# CS_SNS.net
KiCad netlist of a schematic drawn in EAGLE
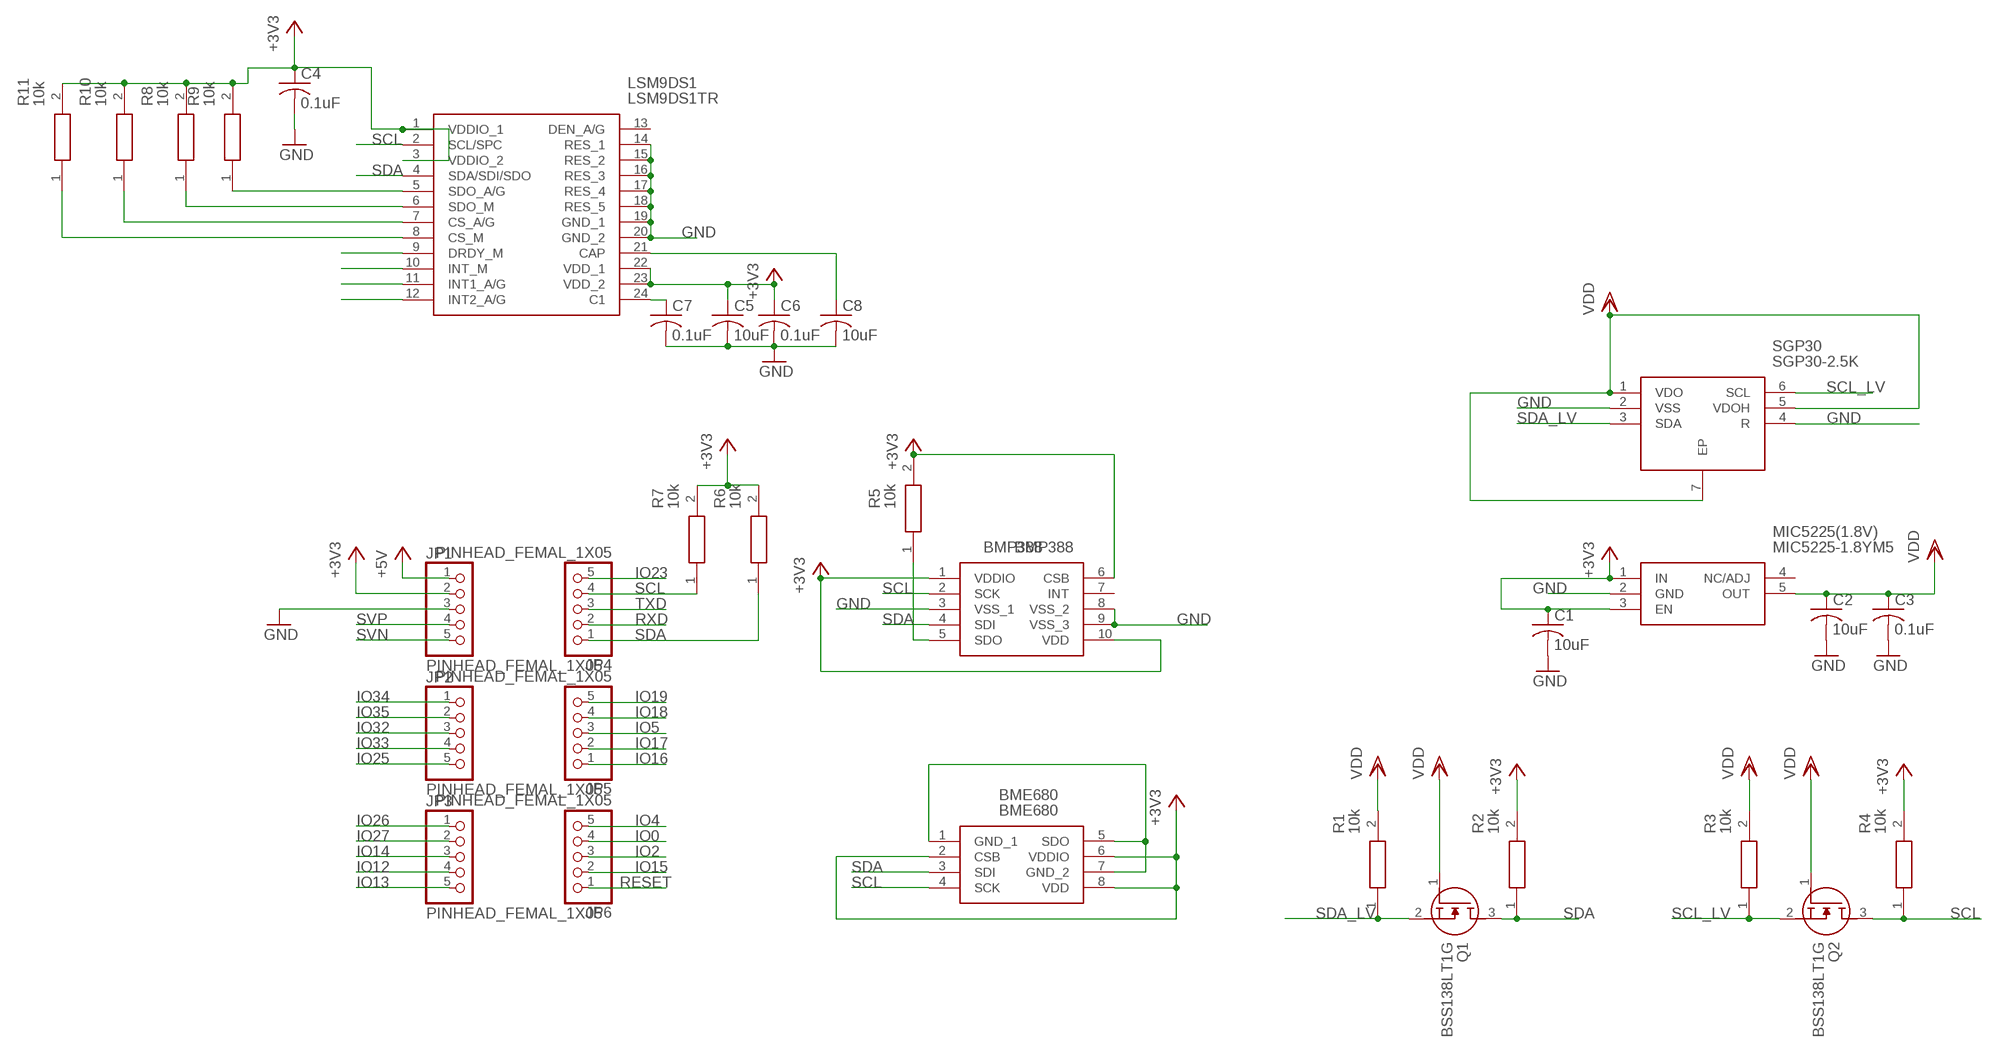
[diagram p0: schematic, sheet 1]

(export (version "E")
  (design (tool "Eeschema 10.0.6"))
  (components
    (comp (ref "BME680")
      (value "BME680")
      (footprint "eagle-import:BME680")
      (fields (field (name "MOUSER_PART_NUMBER") "262-BME680"))
      (libsource (lib "eagle-import") (part "BME680"))
    )
    (comp (ref "BMP388")
      (value "BMP388")
      (footprint "eagle-import:BMP388")
      (fields (field (name "MOUSER_PART_NUMBER") "262-BMP388"))
      (libsource (lib "eagle-import") (part "BMP388"))
    )
    (comp (ref "C1")
      (value "10uF")
      (footprint "eagle-import:C0805")
      (libsource (lib "eagle-import") (part "C-USC0805"))
    )
    (comp (ref "C2")
      (value "10uF")
      (footprint "eagle-import:C0805")
      (libsource (lib "eagle-import") (part "C-USC0805"))
    )
    (comp (ref "C3")
      (value "0.1uF")
      (footprint "eagle-import:C0805")
      (libsource (lib "eagle-import") (part "C-USC0805"))
    )
    (comp (ref "C4")
      (value "0.1uF")
      (footprint "eagle-import:C0805")
      (libsource (lib "eagle-import") (part "C-USC0805"))
    )
    (comp (ref "C5")
      (value "10uF")
      (footprint "eagle-import:C0805")
      (libsource (lib "eagle-import") (part "C-USC0805"))
    )
    (comp (ref "C6")
      (value "0.1uF")
      (footprint "eagle-import:C0805")
      (libsource (lib "eagle-import") (part "C-USC0805"))
    )
    (comp (ref "C7")
      (value "0.1uF")
      (footprint "eagle-import:C0805")
      (libsource (lib "eagle-import") (part "C-USC0805"))
    )
    (comp (ref "C8")
      (value "10uF")
      (footprint "eagle-import:C0805")
      (libsource (lib "eagle-import") (part "C-USC0805"))
    )
    (comp (ref "JP1")
      (value "PINHEAD_FEMAL_1X05")
      (footprint "eagle-import:1X05F")
      (libsource (lib "eagle-import") (part "PINHEAD_FEMAL_1X05"))
    )
    (comp (ref "JP2")
      (value "PINHEAD_FEMAL_1X05")
      (footprint "eagle-import:1X05F")
      (libsource (lib "eagle-import") (part "PINHEAD_FEMAL_1X05"))
    )
    (comp (ref "JP3")
      (value "PINHEAD_FEMAL_1X05")
      (footprint "eagle-import:1X05F")
      (libsource (lib "eagle-import") (part "PINHEAD_FEMAL_1X05"))
    )
    (comp (ref "JP4")
      (value "PINHEAD_FEMAL_1X05")
      (footprint "eagle-import:1X05F")
      (libsource (lib "eagle-import") (part "PINHEAD_FEMAL_1X05"))
    )
    (comp (ref "JP5")
      (value "PINHEAD_FEMAL_1X05")
      (footprint "eagle-import:1X05F")
      (libsource (lib "eagle-import") (part "PINHEAD_FEMAL_1X05"))
    )
    (comp (ref "JP6")
      (value "PINHEAD_FEMAL_1X05")
      (footprint "eagle-import:1X05F")
      (libsource (lib "eagle-import") (part "PINHEAD_FEMAL_1X05"))
    )
    (comp (ref "LSM9DS1")
      (value "LSM9DS1TR")
      (footprint "eagle-import:LGA-24L(3X3.5X1MM)")
      (fields (field (name "MOUSER_PART_NUMBER") "511-LSM9DS1TR") (field (name "RS_PART_NUMBER") "1660908"))
      (libsource (lib "eagle-import") (part "LSM9DS1TR"))
    )
    (comp (ref "MIC5225(1.8V)")
      (value "MIC5225-1.8YM5")
      (footprint "eagle-import:SOT95P280X145-5N")
      (libsource (lib "eagle-import") (part "MIC5225-1.8YM5"))
    )
    (comp (ref "Q1")
      (value "BSS138LT1G")
      (footprint "eagle-import:SOT96P237X111-3N")
      (fields (field (name "MOUSER_PART_NUMBER") "863-BSS138LT1G") (field (name "RS_PART_NUMBER") "5452529P"))
      (libsource (lib "eagle-import") (part "BSS138LT1G"))
    )
    (comp (ref "Q2")
      (value "BSS138LT1G")
      (footprint "eagle-import:SOT96P237X111-3N")
      (fields (field (name "MOUSER_PART_NUMBER") "863-BSS138LT1G") (field (name "RS_PART_NUMBER") "5452529P"))
      (libsource (lib "eagle-import") (part "BSS138LT1G"))
    )
    (comp (ref "R1")
      (value "10k")
      (footprint "eagle-import:RESC2012X60N")
      (fields
        (field (name "MANUFACTURER_PART_NUMBER") "ERA-6AED134V")
        (field (name "MOUSER_PART_NUMBER") "667-ERA-6AED134V")
      )
      (libsource (lib "eagle-import") (part "ERA-6AED134V"))
    )
    (comp (ref "R2")
      (value "10k")
      (footprint "eagle-import:RESC2012X60N")
      (fields
        (field (name "MANUFACTURER_PART_NUMBER") "ERA-6AED134V")
        (field (name "MOUSER_PART_NUMBER") "667-ERA-6AED134V")
      )
      (libsource (lib "eagle-import") (part "ERA-6AED134V"))
    )
    (comp (ref "R3")
      (value "10k")
      (footprint "eagle-import:RESC2012X60N")
      (fields
        (field (name "MANUFACTURER_PART_NUMBER") "ERA-6AED134V")
        (field (name "MOUSER_PART_NUMBER") "667-ERA-6AED134V")
      )
      (libsource (lib "eagle-import") (part "ERA-6AED134V"))
    )
    (comp (ref "R4")
      (value "10k")
      (footprint "eagle-import:RESC2012X60N")
      (fields
        (field (name "MANUFACTURER_PART_NUMBER") "ERA-6AED134V")
        (field (name "MOUSER_PART_NUMBER") "667-ERA-6AED134V")
      )
      (libsource (lib "eagle-import") (part "ERA-6AED134V"))
    )
    (comp (ref "R5")
      (value "10k")
      (footprint "eagle-import:RESC2012X60N")
      (fields
        (field (name "MANUFACTURER_PART_NUMBER") "ERA-6AED134V")
        (field (name "MOUSER_PART_NUMBER") "667-ERA-6AED134V")
      )
      (libsource (lib "eagle-import") (part "ERA-6AED134V"))
    )
    (comp (ref "R6")
      (value "10k")
      (footprint "eagle-import:RESC2012X60N")
      (fields
        (field (name "MANUFACTURER_PART_NUMBER") "ERA-6AED134V")
        (field (name "MOUSER_PART_NUMBER") "667-ERA-6AED134V")
      )
      (libsource (lib "eagle-import") (part "ERA-6AED134V"))
    )
    (comp (ref "R7")
      (value "10k")
      (footprint "eagle-import:RESC2012X60N")
      (fields
        (field (name "MANUFACTURER_PART_NUMBER") "ERA-6AED134V")
        (field (name "MOUSER_PART_NUMBER") "667-ERA-6AED134V")
      )
      (libsource (lib "eagle-import") (part "ERA-6AED134V"))
    )
    (comp (ref "R8")
      (value "10k")
      (footprint "eagle-import:RESC2012X60N")
      (fields
        (field (name "MANUFACTURER_PART_NUMBER") "ERA-6AED134V")
        (field (name "MOUSER_PART_NUMBER") "667-ERA-6AED134V")
      )
      (libsource (lib "eagle-import") (part "ERA-6AED134V"))
    )
    (comp (ref "R9")
      (value "10k")
      (footprint "eagle-import:RESC2012X60N")
      (fields
        (field (name "MANUFACTURER_PART_NUMBER") "ERA-6AED134V")
        (field (name "MOUSER_PART_NUMBER") "667-ERA-6AED134V")
      )
      (libsource (lib "eagle-import") (part "ERA-6AED134V"))
    )
    (comp (ref "R10")
      (value "10k")
      (footprint "eagle-import:RESC2012X60N")
      (fields
        (field (name "MANUFACTURER_PART_NUMBER") "ERA-6AED134V")
        (field (name "MOUSER_PART_NUMBER") "667-ERA-6AED134V")
      )
      (libsource (lib "eagle-import") (part "ERA-6AED134V"))
    )
    (comp (ref "R11")
      (value "10k")
      (footprint "eagle-import:RESC2012X60N")
      (fields
        (field (name "MANUFACTURER_PART_NUMBER") "ERA-6AED134V")
        (field (name "MOUSER_PART_NUMBER") "667-ERA-6AED134V")
      )
      (libsource (lib "eagle-import") (part "ERA-6AED134V"))
    )
    (comp (ref "SGP30")
      (value "SGP30-2.5K")
      (footprint "eagle-import:SON80P245X245X90-7N")
      (fields
        (field (name "MANUFACTURER_PART_NUMBER") "SGP30-2.5k")
        (field (name "MOUSER_PART_NUMBER") "403-SGP30-2.5K")
        (field (name "RS_PART_NUMBER") "1463573")
      )
      (libsource (lib "eagle-import") (part "SGP30-2.5K"))
    )
  )
  (nets
    (net (code "1") (name "+3V3") (class "Default")
      (node (ref "BME680") (pin "2") (pinfunction "CSB_2") (pintype "bidirectional"))
      (node (ref "BME680") (pin "6") (pinfunction "VDDIO_6") (pintype "bidirectional"))
      (node (ref "BME680") (pin "8") (pinfunction "VDD_8") (pintype "bidirectional"))
      (node (ref "BMP388") (pin "1") (pinfunction "VDDIO_1") (pintype "bidirectional"))
      (node (ref "BMP388") (pin "10") (pinfunction "VDD_10") (pintype "bidirectional"))
      (node (ref "BMP388") (pin "6") (pinfunction "CSB_6") (pintype "bidirectional"))
      (node (ref "C1") (pin "1") (pinfunction "1_1") (pintype "passive"))
      (node (ref "C4") (pin "1") (pinfunction "1_1") (pintype "passive"))
      (node (ref "C5") (pin "1") (pinfunction "1_1") (pintype "passive"))
      (node (ref "C6") (pin "1") (pinfunction "1_1") (pintype "passive"))
      (node (ref "JP1") (pin "2") (pinfunction "2_2") (pintype "passive"))
      (node (ref "LSM9DS1") (pin "1") (pinfunction "VDDIO_1_1") (pintype "power_in"))
      (node (ref "LSM9DS1") (pin "22") (pinfunction "VDD_1_22") (pintype "power_in"))
      (node (ref "LSM9DS1") (pin "23") (pinfunction "VDD_2_23") (pintype "power_in"))
      (node (ref "LSM9DS1") (pin "3") (pinfunction "VDDIO_2_3") (pintype "power_in"))
      (node (ref "MIC5225(1.8V)") (pin "1") (pinfunction "IN_1") (pintype "bidirectional"))
      (node (ref "MIC5225(1.8V)") (pin "3") (pinfunction "EN_3") (pintype "bidirectional"))
      (node (ref "R10") (pin "2") (pinfunction "2_2") (pintype "bidirectional"))
      (node (ref "R11") (pin "2") (pinfunction "2_2") (pintype "bidirectional"))
      (node (ref "R2") (pin "2") (pinfunction "2_2") (pintype "bidirectional"))
      (node (ref "R4") (pin "2") (pinfunction "2_2") (pintype "bidirectional"))
      (node (ref "R5") (pin "2") (pinfunction "2_2") (pintype "bidirectional"))
      (node (ref "R6") (pin "2") (pinfunction "2_2") (pintype "bidirectional"))
      (node (ref "R7") (pin "2") (pinfunction "2_2") (pintype "bidirectional"))
      (node (ref "R8") (pin "2") (pinfunction "2_2") (pintype "bidirectional"))
      (node (ref "R9") (pin "2") (pinfunction "2_2") (pintype "bidirectional"))
    )
    (net (code "2") (name "+5V") (class "Default")
      (node (ref "JP1") (pin "1") (pinfunction "1_1") (pintype "passive"))
    )
    (net (code "3") (name "/IO0") (class "Default")
      (node (ref "JP6") (pin "4") (pinfunction "4_4") (pintype "passive"))
    )
    (net (code "4") (name "/IO2") (class "Default")
      (node (ref "JP6") (pin "3") (pinfunction "3_3") (pintype "passive"))
    )
    (net (code "5") (name "/IO4") (class "Default")
      (node (ref "JP6") (pin "5") (pinfunction "5_5") (pintype "passive"))
    )
    (net (code "6") (name "/IO5") (class "Default")
      (node (ref "JP5") (pin "3") (pinfunction "3_3") (pintype "passive"))
    )
    (net (code "7") (name "/IO12") (class "Default")
      (node (ref "JP3") (pin "4") (pinfunction "4_4") (pintype "passive"))
    )
    (net (code "8") (name "/IO13") (class "Default")
      (node (ref "JP3") (pin "5") (pinfunction "5_5") (pintype "passive"))
    )
    (net (code "9") (name "/IO14") (class "Default")
      (node (ref "JP3") (pin "3") (pinfunction "3_3") (pintype "passive"))
    )
    (net (code "10") (name "/IO15") (class "Default")
      (node (ref "JP6") (pin "2") (pinfunction "2_2") (pintype "passive"))
    )
    (net (code "11") (name "/IO16") (class "Default")
      (node (ref "JP5") (pin "1") (pinfunction "1_1") (pintype "passive"))
    )
    (net (code "12") (name "/IO17") (class "Default")
      (node (ref "JP5") (pin "2") (pinfunction "2_2") (pintype "passive"))
    )
    (net (code "13") (name "/IO18") (class "Default")
      (node (ref "JP5") (pin "4") (pinfunction "4_4") (pintype "passive"))
    )
    (net (code "14") (name "/IO19") (class "Default")
      (node (ref "JP5") (pin "5") (pinfunction "5_5") (pintype "passive"))
    )
    (net (code "15") (name "/IO23") (class "Default")
      (node (ref "JP4") (pin "5") (pinfunction "5_5") (pintype "passive"))
    )
    (net (code "16") (name "/IO25") (class "Default")
      (node (ref "JP2") (pin "5") (pinfunction "5_5") (pintype "passive"))
    )
    (net (code "17") (name "/IO26") (class "Default")
      (node (ref "JP3") (pin "1") (pinfunction "1_1") (pintype "passive"))
    )
    (net (code "18") (name "/IO27") (class "Default")
      (node (ref "JP3") (pin "2") (pinfunction "2_2") (pintype "passive"))
    )
    (net (code "19") (name "/IO32") (class "Default")
      (node (ref "JP2") (pin "3") (pinfunction "3_3") (pintype "passive"))
    )
    (net (code "20") (name "/IO33") (class "Default")
      (node (ref "JP2") (pin "4") (pinfunction "4_4") (pintype "passive"))
    )
    (net (code "21") (name "/IO34") (class "Default")
      (node (ref "JP2") (pin "1") (pinfunction "1_1") (pintype "passive"))
    )
    (net (code "22") (name "/IO35") (class "Default")
      (node (ref "JP2") (pin "2") (pinfunction "2_2") (pintype "passive"))
    )
    (net (code "23") (name "/RESET") (class "Default")
      (node (ref "JP6") (pin "1") (pinfunction "1_1") (pintype "passive"))
    )
    (net (code "24") (name "/RXD") (class "Default")
      (node (ref "JP4") (pin "2") (pinfunction "2_2") (pintype "passive"))
    )
    (net (code "25") (name "/SCL") (class "Default")
      (node (ref "BME680") (pin "4") (pinfunction "SCK_4") (pintype "bidirectional"))
      (node (ref "BMP388") (pin "2") (pinfunction "SCK_2") (pintype "bidirectional"))
      (node (ref "JP4") (pin "4") (pinfunction "4_4") (pintype "passive"))
      (node (ref "LSM9DS1") (pin "2") (pinfunction "SCL/SPC_2") (pintype "output"))
      (node (ref "Q2") (pin "3") (pinfunction "D_3") (pintype "bidirectional"))
      (node (ref "R4") (pin "1") (pinfunction "1_1") (pintype "bidirectional"))
      (node (ref "R7") (pin "1") (pinfunction "1_1") (pintype "bidirectional"))
    )
    (net (code "26") (name "/SCL_LV") (class "Default")
      (node (ref "Q2") (pin "2") (pinfunction "S_2") (pintype "bidirectional"))
      (node (ref "R3") (pin "1") (pinfunction "1_1") (pintype "bidirectional"))
      (node (ref "SGP30") (pin "6") (pinfunction "SCL_6") (pintype "bidirectional"))
    )
    (net (code "27") (name "/SDA") (class "Default")
      (node (ref "BME680") (pin "3") (pinfunction "SDI_3") (pintype "bidirectional"))
      (node (ref "BMP388") (pin "4") (pinfunction "SDI_4") (pintype "bidirectional"))
      (node (ref "JP4") (pin "1") (pinfunction "1_1") (pintype "passive"))
      (node (ref "LSM9DS1") (pin "4") (pinfunction "SDA/SDI/SDO_4") (pintype "bidirectional"))
      (node (ref "Q1") (pin "3") (pinfunction "D_3") (pintype "bidirectional"))
      (node (ref "R2") (pin "1") (pinfunction "1_1") (pintype "bidirectional"))
      (node (ref "R6") (pin "1") (pinfunction "1_1") (pintype "bidirectional"))
    )
    (net (code "28") (name "/SDA_LV") (class "Default")
      (node (ref "Q1") (pin "2") (pinfunction "S_2") (pintype "bidirectional"))
      (node (ref "R1") (pin "1") (pinfunction "1_1") (pintype "bidirectional"))
      (node (ref "SGP30") (pin "3") (pinfunction "SDA_3") (pintype "bidirectional"))
    )
    (net (code "29") (name "/SVN") (class "Default")
      (node (ref "JP1") (pin "5") (pinfunction "5_5") (pintype "passive"))
    )
    (net (code "30") (name "/SVP") (class "Default")
      (node (ref "JP1") (pin "4") (pinfunction "4_4") (pintype "passive"))
    )
    (net (code "31") (name "/TXD") (class "Default")
      (node (ref "JP4") (pin "3") (pinfunction "3_3") (pintype "passive"))
    )
    (net (code "32") (name "GND") (class "Default")
      (node (ref "BMP388") (pin "3") (pinfunction "VSS_1_3") (pintype "bidirectional"))
      (node (ref "BMP388") (pin "8") (pinfunction "VSS_2_8") (pintype "bidirectional"))
      (node (ref "BMP388") (pin "9") (pinfunction "VSS_3_9") (pintype "bidirectional"))
      (node (ref "C1") (pin "2") (pinfunction "2_2") (pintype "passive"))
      (node (ref "C2") (pin "2") (pinfunction "2_2") (pintype "passive"))
      (node (ref "C3") (pin "2") (pinfunction "2_2") (pintype "passive"))
      (node (ref "C4") (pin "2") (pinfunction "2_2") (pintype "passive"))
      (node (ref "C5") (pin "2") (pinfunction "2_2") (pintype "passive"))
      (node (ref "C6") (pin "2") (pinfunction "2_2") (pintype "passive"))
      (node (ref "C7") (pin "2") (pinfunction "2_2") (pintype "passive"))
      (node (ref "C8") (pin "2") (pinfunction "2_2") (pintype "passive"))
      (node (ref "JP1") (pin "3") (pinfunction "3_3") (pintype "passive"))
      (node (ref "LSM9DS1") (pin "14") (pinfunction "RES_1_14") (pintype "power_in"))
      (node (ref "LSM9DS1") (pin "15") (pinfunction "RES_2_15") (pintype "power_in"))
      (node (ref "LSM9DS1") (pin "16") (pinfunction "RES_3_16") (pintype "power_in"))
      (node (ref "LSM9DS1") (pin "17") (pinfunction "RES_4_17") (pintype "power_in"))
      (node (ref "LSM9DS1") (pin "18") (pinfunction "RES_5_18") (pintype "power_in"))
      (node (ref "LSM9DS1") (pin "19") (pinfunction "GND_1_19") (pintype "power_in"))
      (node (ref "LSM9DS1") (pin "20") (pinfunction "GND_2_20") (pintype "power_in"))
      (node (ref "MIC5225(1.8V)") (pin "2") (pinfunction "GND_2") (pintype "bidirectional"))
      (node (ref "SGP30") (pin "2") (pinfunction "VSS_2") (pintype "power_in"))
      (node (ref "SGP30") (pin "4") (pinfunction "R_4") (pintype "power_in"))
    )
    (net (code "33") (name "Net-(BME680-GND_1)") (class "Default")
      (node (ref "BME680") (pin "1") (pinfunction "GND_1_1") (pintype "bidirectional"))
      (node (ref "BME680") (pin "5") (pinfunction "SDO_5") (pintype "bidirectional"))
      (node (ref "BME680") (pin "7") (pinfunction "GND_2_7") (pintype "bidirectional"))
    )
    (net (code "34") (name "Net-(BMP388-SDO)") (class "Default")
      (node (ref "BMP388") (pin "5") (pinfunction "SDO_5") (pintype "bidirectional"))
      (node (ref "R5") (pin "1") (pinfunction "1_1") (pintype "bidirectional"))
    )
    (net (code "35") (name "Net-(LSM9DS1-C1)") (class "Default")
      (node (ref "C7") (pin "1") (pinfunction "1_1") (pintype "passive"))
      (node (ref "LSM9DS1") (pin "24") (pinfunction "C1_24") (pintype "bidirectional"))
    )
    (net (code "36") (name "Net-(LSM9DS1-CAP)") (class "Default")
      (node (ref "C8") (pin "1") (pinfunction "1_1") (pintype "passive"))
      (node (ref "LSM9DS1") (pin "21") (pinfunction "CAP_21") (pintype "power_in"))
    )
    (net (code "37") (name "Net-(LSM9DS1-CS_A{slash}G)") (class "Default")
      (node (ref "LSM9DS1") (pin "7") (pinfunction "CS_A/G_7") (pintype "bidirectional"))
      (node (ref "R10") (pin "1") (pinfunction "1_1") (pintype "bidirectional"))
    )
    (net (code "38") (name "Net-(LSM9DS1-CS_M)") (class "Default")
      (node (ref "LSM9DS1") (pin "8") (pinfunction "CS_M_8") (pintype "bidirectional"))
      (node (ref "R11") (pin "1") (pinfunction "1_1") (pintype "bidirectional"))
    )
    (net (code "39") (name "Net-(LSM9DS1-SDO_A{slash}G)") (class "Default")
      (node (ref "LSM9DS1") (pin "5") (pinfunction "SDO_A/G_5") (pintype "output"))
      (node (ref "R9") (pin "1") (pinfunction "1_1") (pintype "bidirectional"))
    )
    (net (code "40") (name "Net-(LSM9DS1-SDO_M)") (class "Default")
      (node (ref "LSM9DS1") (pin "6") (pinfunction "SDO_M_6") (pintype "output"))
      (node (ref "R8") (pin "1") (pinfunction "1_1") (pintype "bidirectional"))
    )
    (net (code "41") (name "VDD") (class "Default")
      (node (ref "C2") (pin "1") (pinfunction "1_1") (pintype "passive"))
      (node (ref "C3") (pin "1") (pinfunction "1_1") (pintype "passive"))
      (node (ref "MIC5225(1.8V)") (pin "5") (pinfunction "OUT_5") (pintype "bidirectional"))
      (node (ref "Q1") (pin "1") (pinfunction "G_1") (pintype "bidirectional"))
      (node (ref "Q2") (pin "1") (pinfunction "G_1") (pintype "bidirectional"))
      (node (ref "R1") (pin "2") (pinfunction "2_2") (pintype "bidirectional"))
      (node (ref "R3") (pin "2") (pinfunction "2_2") (pintype "bidirectional"))
      (node (ref "SGP30") (pin "1") (pinfunction "VDO_1") (pintype "power_in"))
      (node (ref "SGP30") (pin "5") (pinfunction "VDOH_5") (pintype "power_in"))
      (node (ref "SGP30") (pin "7") (pinfunction "EP_7") (pintype "bidirectional"))
    )
    (net (code "42") (name "unconnected-(BMP388-INT-Pad7)") (class "Default")
      (node (ref "BMP388") (pin "7") (pinfunction "INT_7") (pintype "bidirectional"))
    )
    (net (code "43") (name "unconnected-(LSM9DS1-DEN_A{slash}G-Pad13)") (class "Default")
      (node (ref "LSM9DS1") (pin "13") (pinfunction "DEN_A/G_13") (pintype "bidirectional"))
    )
    (net (code "44") (name "unconnected-(LSM9DS1-DRDY_M-Pad9)") (class "Default")
      (node (ref "LSM9DS1") (pin "9") (pinfunction "DRDY_M_9") (pintype "bidirectional"))
    )
    (net (code "45") (name "unconnected-(LSM9DS1-INT1_A{slash}G-Pad11)") (class "Default")
      (node (ref "LSM9DS1") (pin "11") (pinfunction "INT1_A/G_11") (pintype "bidirectional"))
    )
    (net (code "46") (name "unconnected-(LSM9DS1-INT2_A{slash}G-Pad12)") (class "Default")
      (node (ref "LSM9DS1") (pin "12") (pinfunction "INT2_A/G_12") (pintype "bidirectional"))
    )
    (net (code "47") (name "unconnected-(LSM9DS1-INT_M-Pad10)") (class "Default")
      (node (ref "LSM9DS1") (pin "10") (pinfunction "INT_M_10") (pintype "bidirectional"))
    )
    (net (code "48") (name "unconnected-(MIC5225(1.8V)-NC{slash}ADJ-Pad4)") (class "Default")
      (node (ref "MIC5225(1.8V)") (pin "4") (pinfunction "NC/ADJ_4") (pintype "bidirectional"))
    )
  )
)
